# RS485.net
KiCad netlist of a schematic drawn in Altium Designer
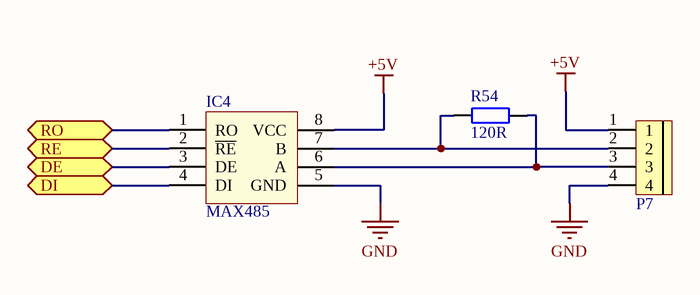
[diagram p0: RS485.SchDoc]

(export (version "E")
  (design (tool "Eeschema 10.0.6"))
  (components
    (comp (ref "IC4")
      (value "MAX485")
      (footprint "SO-8")
      (description "RS232 - RS485 (Same sn75176)")
      (libsource (lib "syhaunguyen") (part "MAX485"))
    )
    (comp (ref "P7")
      (value "CON 4 EDG5.08")
      (footprint "CON 4 4EDG5.08")
      (description "Cắm")
      (libsource (lib "Altium_Lib_by_KhueNguyenCreator") (part "CON 4 EDG5.08"))
    )
    (comp (ref "R54")
      (value "120R")
      (footprint "tro smd 0805")
      (description "Dán")
      (libsource (lib "Altium_Lib_by_KhueNguyenCreator") (part "Tro 0805 5% 120R"))
    )
  )
  (nets
    (net (code "1") (name "+5V") (class "Default")
      (node (ref "IC4") (pin "8") (pinfunction "VCC_8") (pintype "passive"))
      (node (ref "P7") (pin "1") (pinfunction "1_1") (pintype "passive"))
    )
    (net (code "2") (name "/DE") (class "Default")
      (node (ref "IC4") (pin "3") (pinfunction "DE_3") (pintype "passive"))
    )
    (net (code "3") (name "/DI") (class "Default")
      (node (ref "IC4") (pin "4") (pinfunction "DI_4") (pintype "passive"))
    )
    (net (code "4") (name "/RE") (class "Default")
      (node (ref "IC4") (pin "2") (pinfunction "~{RE}_2") (pintype "passive"))
    )
    (net (code "5") (name "/RO") (class "Default")
      (node (ref "IC4") (pin "1") (pinfunction "RO_1") (pintype "passive"))
    )
    (net (code "6") (name "GND") (class "Default")
      (node (ref "IC4") (pin "5") (pinfunction "GND_5") (pintype "passive"))
      (node (ref "P7") (pin "4") (pinfunction "4_4") (pintype "passive"))
    )
    (net (code "7") (name "Net-(IC4-A)") (class "Default")
      (node (ref "IC4") (pin "6") (pinfunction "A_6") (pintype "passive"))
      (node (ref "P7") (pin "3") (pinfunction "3_3") (pintype "passive"))
      (node (ref "R54") (pin "2") (pinfunction "2_2") (pintype "passive"))
    )
    (net (code "8") (name "Net-(IC4-B)") (class "Default")
      (node (ref "IC4") (pin "7") (pinfunction "B_7") (pintype "passive"))
      (node (ref "P7") (pin "2") (pinfunction "2_2") (pintype "passive"))
      (node (ref "R54") (pin "1") (pinfunction "1_1") (pintype "passive"))
    )
  )
)
